# MaTouch_ESP32-S3_Rotary_IPS_Display_with.net
KiCad netlist of a schematic drawn in EAGLE
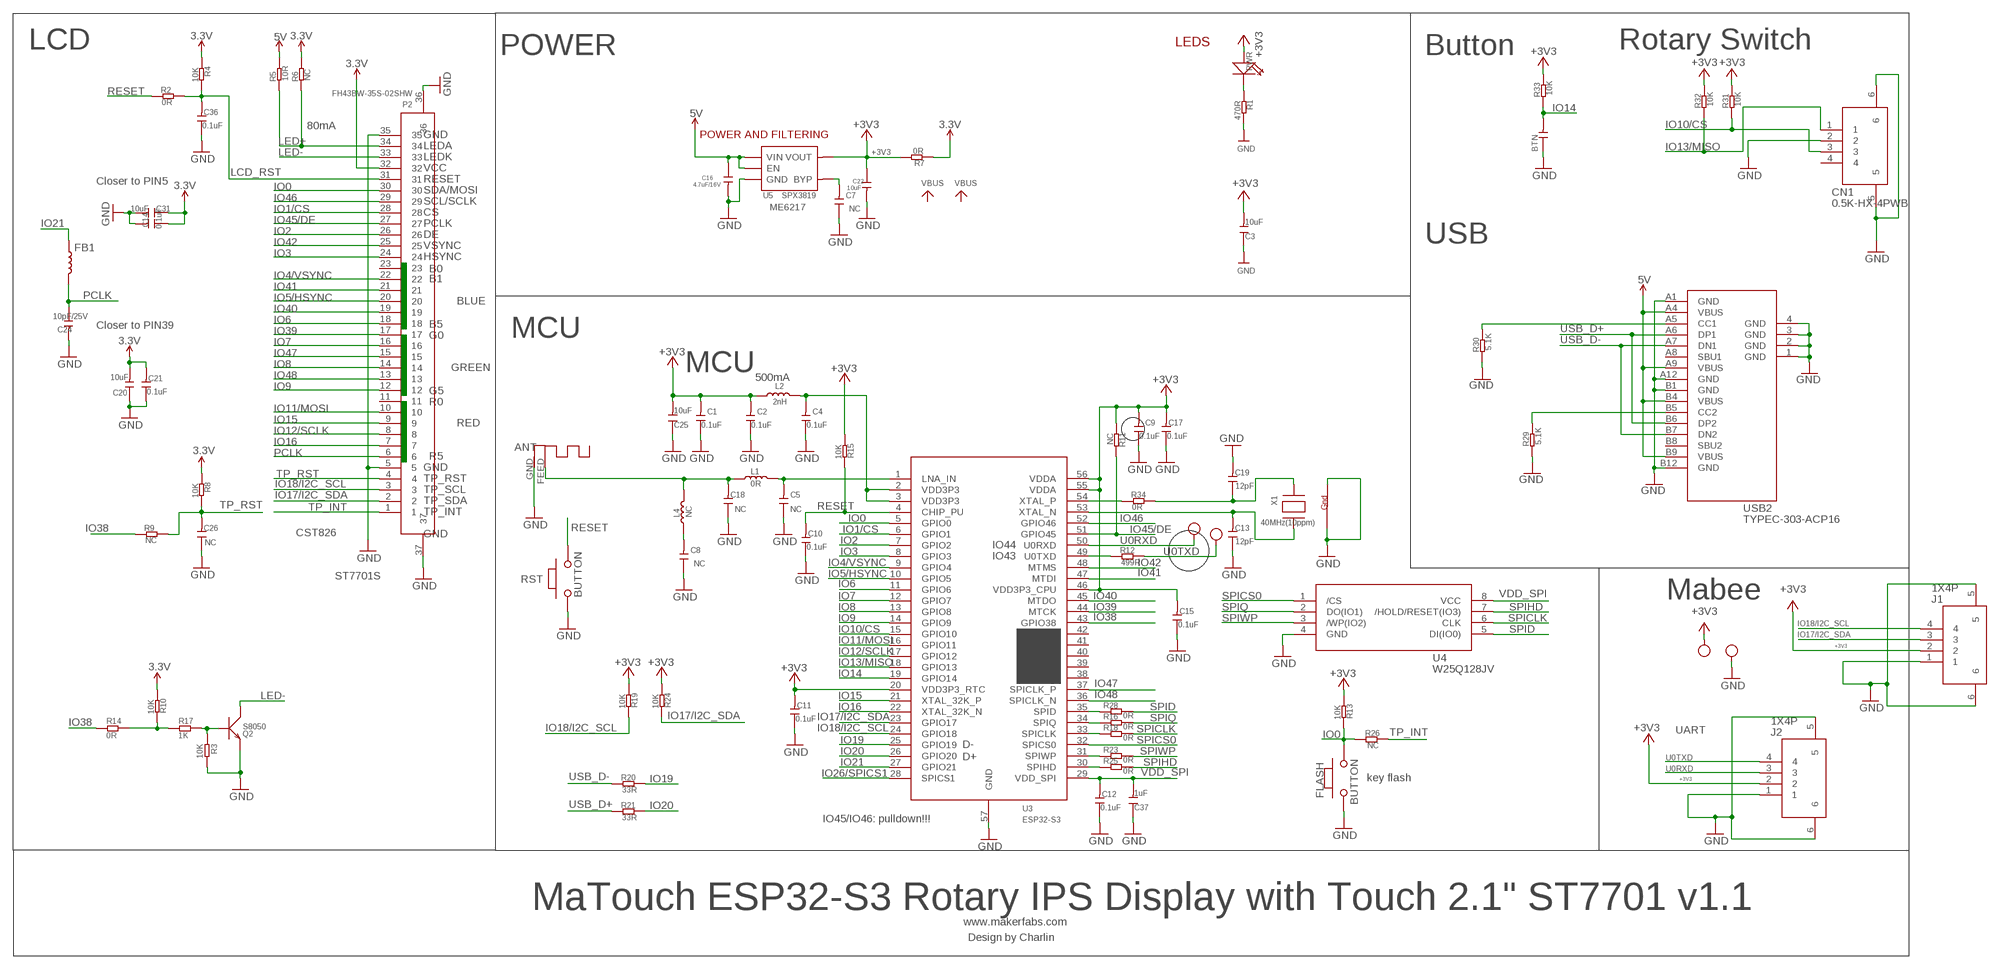
[diagram p0: schematic, sheet 1]

(export (version "E")
  (design (tool "Eeschema 10.0.6"))
  (components
    (comp (ref "3V3")
      (value "TEST-POINT'4545'")
      (footprint "eagle-import:TP-D45MIL")
      (fields (field (name "PARTNO") "DNP") (field (name "PARTNO_1") "DNP"))
      (libsource (lib "eagle-import") (part "TEST-POINT'4545'"))
    )
    (comp (ref "ANT1")
      (value "ANTENNA")
      (footprint "eagle-import:RN-ANT")
      (libsource (lib "eagle-import") (part "ANTENNA"))
    )
    (comp (ref "BTN")
      (value "C'5.08'")
      (footprint "eagle-import:CERAMIC-5.08")
      (libsource (lib "eagle-import") (part "C'5.08'"))
    )
    (comp (ref "C1")
      (value "0.1uF")
      (footprint "eagle-import:DISCRETE_C0402")
      (libsource (lib "eagle-import") (part "DISCRETE_C-0402"))
    )
    (comp (ref "C2")
      (value "0.1uF")
      (footprint "eagle-import:DISCRETE_C0402")
      (libsource (lib "eagle-import") (part "DISCRETE_C-0402"))
    )
    (comp (ref "C3")
      (value "10uF")
      (footprint "eagle-import:DISCRETE_C0603")
      (libsource (lib "eagle-import") (part "DISCRETE_C-0603"))
    )
    (comp (ref "C4")
      (value "0.1uF")
      (footprint "eagle-import:DISCRETE_C0402")
      (libsource (lib "eagle-import") (part "DISCRETE_C-0402"))
    )
    (comp (ref "C5")
      (value "NC")
      (footprint "eagle-import:DISCRETE_C0402")
      (libsource (lib "eagle-import") (part "DISCRETE_C-0402"))
    )
    (comp (ref "C7")
      (value "NC")
      (footprint "eagle-import:DISCRETE_C0402")
      (libsource (lib "eagle-import") (part "DISCRETE_C-0402"))
    )
    (comp (ref "C8")
      (value "NC")
      (footprint "eagle-import:DISCRETE_C0402")
      (libsource (lib "eagle-import") (part "DISCRETE_C-0402"))
    )
    (comp (ref "C9")
      (value "0.1uF")
      (footprint "eagle-import:DISCRETE_C0402")
      (libsource (lib "eagle-import") (part "DISCRETE_C-0402"))
    )
    (comp (ref "C10")
      (value "0.1uF")
      (footprint "eagle-import:DISCRETE_C0402")
      (libsource (lib "eagle-import") (part "DISCRETE_C-0402"))
    )
    (comp (ref "C11")
      (value "0.1uF")
      (footprint "eagle-import:DISCRETE_C0402")
      (libsource (lib "eagle-import") (part "DISCRETE_C-0402"))
    )
    (comp (ref "C12")
      (value "0.1uF")
      (footprint "eagle-import:DISCRETE_C0402")
      (libsource (lib "eagle-import") (part "DISCRETE_C-0402"))
    )
    (comp (ref "C13")
      (value "12pF")
      (footprint "eagle-import:DISCRETE_C0402")
      (libsource (lib "eagle-import") (part "DISCRETE_C-0402"))
    )
    (comp (ref "C14")
      (value "0.1uF")
      (footprint "eagle-import:DISCRETE_C0402")
      (libsource (lib "eagle-import") (part "DISCRETE_C-0402"))
    )
    (comp (ref "C15")
      (value "0.1uF")
      (footprint "eagle-import:DISCRETE_C0402")
      (libsource (lib "eagle-import") (part "DISCRETE_C-0402"))
    )
    (comp (ref "C16")
      (value "4.7uF/16V")
      (footprint "eagle-import:0603")
      (libsource (lib "eagle-import") (part "C-0603"))
    )
    (comp (ref "C17")
      (value "0.1uF")
      (footprint "eagle-import:DISCRETE_C0402")
      (libsource (lib "eagle-import") (part "DISCRETE_C-0402"))
    )
    (comp (ref "C18")
      (value "NC")
      (footprint "eagle-import:DISCRETE_C0402")
      (libsource (lib "eagle-import") (part "DISCRETE_C-0402"))
    )
    (comp (ref "C19")
      (value "12pF")
      (footprint "eagle-import:DISCRETE_C0402")
      (libsource (lib "eagle-import") (part "DISCRETE_C-0402"))
    )
    (comp (ref "C20")
      (value "10uF")
      (footprint "eagle-import:DISCRETE_C0603")
      (libsource (lib "eagle-import") (part "DISCRETE_C-0603"))
    )
    (comp (ref "C21")
      (value "0.1uF")
      (footprint "eagle-import:DISCRETE_C0402")
      (libsource (lib "eagle-import") (part "DISCRETE_C-0402"))
    )
    (comp (ref "C22")
      (value "10uF")
      (footprint "eagle-import:0603")
      (libsource (lib "eagle-import") (part "C-0603"))
    )
    (comp (ref "C24")
      (value "10pF/25V")
      (footprint "eagle-import:DISCRETE_C0402")
      (libsource (lib "eagle-import") (part "DISCRETE_C-0402"))
    )
    (comp (ref "C25")
      (value "10uF")
      (footprint "eagle-import:DISCRETE_C0603")
      (libsource (lib "eagle-import") (part "DISCRETE_C-0603"))
    )
    (comp (ref "C26")
      (value "NC")
      (footprint "eagle-import:DISCRETE_C0402")
      (libsource (lib "eagle-import") (part "DISCRETE_C-0402"))
    )
    (comp (ref "C31")
      (value "10uF")
      (footprint "eagle-import:DISCRETE_C0603")
      (libsource (lib "eagle-import") (part "DISCRETE_C-0603"))
    )
    (comp (ref "C36")
      (value "0.1uF")
      (footprint "eagle-import:DISCRETE_C0402")
      (libsource (lib "eagle-import") (part "DISCRETE_C-0402"))
    )
    (comp (ref "C37")
      (value "1uF")
      (footprint "eagle-import:DISCRETE_C0603")
      (libsource (lib "eagle-import") (part "DISCRETE_C-0603"))
    )
    (comp (ref "CN1")
      (value "0.5K-HX-4PWB")
      (footprint "eagle-import:0.5K-HX-4PWB")
      (libsource (lib "eagle-import") (part "0.5K-HX-4PWB"))
    )
    (comp (ref "FB1")
      (value "INDUCTORFB-30OHM")
      (footprint "eagle-import:0603")
      (libsource (lib "eagle-import") (part "INDUCTORFB-30OHM"))
    )
    (comp (ref "FLASH")
      (value "BUTTON")
      (footprint "eagle-import:157SW")
      (libsource (lib "eagle-import") (part "PB157"))
    )
    (comp (ref "GND")
      (value "TEST-POINT'4545'")
      (footprint "eagle-import:TP-D45MIL")
      (fields (field (name "PARTNO") "DNP") (field (name "PARTNO_1") "DNP"))
      (libsource (lib "eagle-import") (part "TEST-POINT'4545'"))
    )
    (comp (ref "J1")
      (value "1X4P")
      (footprint "eagle-import:1X4P-SMT1.25MM")
      (libsource (lib "eagle-import") (part "1X4P"))
    )
    (comp (ref "J2")
      (value "1X4P")
      (footprint "eagle-import:1X4P-SMT1.25MM")
      (libsource (lib "eagle-import") (part "1X4P"))
    )
    (comp (ref "L1")
      (value "0R")
      (footprint "eagle-import:DISCRETE_L0402")
      (libsource (lib "eagle-import") (part "DISCRETE_L0402"))
    )
    (comp (ref "L2")
      (value "2nH")
      (footprint "eagle-import:DISCRETE_L0603")
      (libsource (lib "eagle-import") (part "DISCRETE_L0603"))
    )
    (comp (ref "L4")
      (value "NC")
      (footprint "eagle-import:DISCRETE_L0402")
      (libsource (lib "eagle-import") (part "DISCRETE_L0402"))
    )
    (comp (ref "P2")
      (value "FH43BW-35S-02SHW")
      (footprint "eagle-import:1_35P-SMT0.4MM")
      (libsource (lib "eagle-import") (part "FH43BW-35S-02SHW"))
    )
    (comp (ref "PWR")
      (value "DISCRETE_LED0603")
      (footprint "eagle-import:DISCRETE_LED-0603")
      (libsource (lib "eagle-import") (part "DISCRETE_LED0603"))
    )
    (comp (ref "Q2")
      (value "S8050")
      (footprint "eagle-import:SOT23")
      (libsource (lib "eagle-import") (part "TRANSISTOR-NPN-SOT23"))
    )
    (comp (ref "R1")
      (value "470R")
      (footprint "eagle-import:DISCRETE_R0402")
      (libsource (lib "eagle-import") (part "DISCRETE_R-0402"))
    )
    (comp (ref "R2")
      (value "0R")
      (footprint "eagle-import:DISCRETE_R0402")
      (libsource (lib "eagle-import") (part "DISCRETE_R-0402"))
    )
    (comp (ref "R3")
      (value "10K")
      (footprint "eagle-import:DISCRETE_R0402")
      (libsource (lib "eagle-import") (part "DISCRETE_R-0402"))
    )
    (comp (ref "R4")
      (value "10K")
      (footprint "eagle-import:DISCRETE_R0402")
      (libsource (lib "eagle-import") (part "DISCRETE_R-0402"))
    )
    (comp (ref "R5")
      (value "10R")
      (footprint "eagle-import:DISCRETE_R0402")
      (libsource (lib "eagle-import") (part "DISCRETE_R-0402"))
    )
    (comp (ref "R6")
      (value "NC")
      (footprint "eagle-import:DISCRETE_R0402")
      (libsource (lib "eagle-import") (part "DISCRETE_R-0402"))
    )
    (comp (ref "R7")
      (value "0R")
      (footprint "eagle-import:DISCRETE_R0402")
      (libsource (lib "eagle-import") (part "DISCRETE_R-0402"))
    )
    (comp (ref "R8")
      (value "10K")
      (footprint "eagle-import:DISCRETE_R0402")
      (libsource (lib "eagle-import") (part "DISCRETE_R-0402"))
    )
    (comp (ref "R9")
      (value "NC")
      (footprint "eagle-import:DISCRETE_R0402")
      (libsource (lib "eagle-import") (part "DISCRETE_R-0402"))
    )
    (comp (ref "R10")
      (value "10K")
      (footprint "eagle-import:DISCRETE_R0402")
      (libsource (lib "eagle-import") (part "DISCRETE_R-0402"))
    )
    (comp (ref "R11")
      (value "NC")
      (footprint "eagle-import:DISCRETE_R0402")
      (libsource (lib "eagle-import") (part "DISCRETE_R-0402"))
    )
    (comp (ref "R12")
      (value "499R")
      (footprint "eagle-import:DISCRETE_R0402")
      (libsource (lib "eagle-import") (part "DISCRETE_R-0402"))
    )
    (comp (ref "R13")
      (value "10K")
      (footprint "eagle-import:DISCRETE_R0402")
      (libsource (lib "eagle-import") (part "DISCRETE_R-0402"))
    )
    (comp (ref "R14")
      (value "0R")
      (footprint "eagle-import:DISCRETE_R0402")
      (libsource (lib "eagle-import") (part "DISCRETE_R-0402"))
    )
    (comp (ref "R15")
      (value "10K")
      (footprint "eagle-import:DISCRETE_R0402")
      (libsource (lib "eagle-import") (part "DISCRETE_R-0402"))
    )
    (comp (ref "R16")
      (value "0R")
      (footprint "eagle-import:DISCRETE_R0402")
      (libsource (lib "eagle-import") (part "DISCRETE_R-0402"))
    )
    (comp (ref "R17")
      (value "1K")
      (footprint "eagle-import:DISCRETE_R0402")
      (libsource (lib "eagle-import") (part "DISCRETE_R-0402"))
    )
    (comp (ref "R18")
      (value "0R")
      (footprint "eagle-import:DISCRETE_R0402")
      (libsource (lib "eagle-import") (part "DISCRETE_R-0402"))
    )
    (comp (ref "R19")
      (value "10K")
      (footprint "eagle-import:DISCRETE_R0402")
      (libsource (lib "eagle-import") (part "DISCRETE_R-0402"))
    )
    (comp (ref "R20")
      (value "33R")
      (footprint "eagle-import:DISCRETE_R0402")
      (libsource (lib "eagle-import") (part "DISCRETE_R-0402"))
    )
    (comp (ref "R21")
      (value "33R")
      (footprint "eagle-import:DISCRETE_R0402")
      (libsource (lib "eagle-import") (part "DISCRETE_R-0402"))
    )
    (comp (ref "R23")
      (value "0R")
      (footprint "eagle-import:DISCRETE_R0402")
      (libsource (lib "eagle-import") (part "DISCRETE_R-0402"))
    )
    (comp (ref "R24")
      (value "10K")
      (footprint "eagle-import:DISCRETE_R0402")
      (libsource (lib "eagle-import") (part "DISCRETE_R-0402"))
    )
    (comp (ref "R25")
      (value "0R")
      (footprint "eagle-import:DISCRETE_R0402")
      (libsource (lib "eagle-import") (part "DISCRETE_R-0402"))
    )
    (comp (ref "R26")
      (value "NC")
      (footprint "eagle-import:DISCRETE_R0402")
      (libsource (lib "eagle-import") (part "DISCRETE_R-0402"))
    )
    (comp (ref "R28")
      (value "0R")
      (footprint "eagle-import:DISCRETE_R0402")
      (libsource (lib "eagle-import") (part "DISCRETE_R-0402"))
    )
    (comp (ref "R29")
      (value "5.1K")
      (footprint "eagle-import:DISCRETE_R0402")
      (libsource (lib "eagle-import") (part "DISCRETE_R-0402"))
    )
    (comp (ref "R30")
      (value "5.1K")
      (footprint "eagle-import:DISCRETE_R0402")
      (libsource (lib "eagle-import") (part "DISCRETE_R-0402"))
    )
    (comp (ref "R31")
      (value "10K")
      (footprint "eagle-import:DISCRETE_R0402")
      (libsource (lib "eagle-import") (part "DISCRETE_R-0402"))
    )
    (comp (ref "R32")
      (value "10K")
      (footprint "eagle-import:DISCRETE_R0402")
      (libsource (lib "eagle-import") (part "DISCRETE_R-0402"))
    )
    (comp (ref "R33")
      (value "10K")
      (footprint "eagle-import:DISCRETE_R0402")
      (libsource (lib "eagle-import") (part "DISCRETE_R-0402"))
    )
    (comp (ref "R34")
      (value "0R")
      (footprint "eagle-import:DISCRETE_R0402")
      (libsource (lib "eagle-import") (part "DISCRETE_R-0402"))
    )
    (comp (ref "RST")
      (value "BUTTON")
      (footprint "eagle-import:157SW")
      (libsource (lib "eagle-import") (part "PB157"))
    )
    (comp (ref "RX")
      (value "TEST-POINT'4545'")
      (footprint "eagle-import:TP-D45MIL")
      (fields (field (name "PARTNO") "DNP") (field (name "PARTNO_1") "DNP"))
      (libsource (lib "eagle-import") (part "TEST-POINT'4545'"))
    )
    (comp (ref "TX")
      (value "TEST-POINT'4545'")
      (footprint "eagle-import:TP-D45MIL")
      (fields (field (name "PARTNO") "DNP") (field (name "PARTNO_1") "DNP"))
      (libsource (lib "eagle-import") (part "TEST-POINT'4545'"))
    )
    (comp (ref "U3")
      (value "ESP32-S3")
      (footprint "eagle-import:QFN56-7_7MM")
      (libsource (lib "eagle-import") (part "ESP32-S3"))
    )
    (comp (ref "U4")
      (value "W25Q128JV")
      (footprint "eagle-import:SOIC-8-208MIL")
      (libsource (lib "eagle-import") (part "W25Q128JV"))
    )
    (comp (ref "U5")
      (value "SPX3819")
      (footprint "eagle-import:SOT23-5")
      (libsource (lib "eagle-import") (part "SPX3819"))
    )
    (comp (ref "USB2")
      (value "TYPEC-303-ACP16")
      (footprint "eagle-import:TYPEC-303-SMD16")
      (libsource (lib "eagle-import") (part "TYPEC-303-ACP16"))
    )
    (comp (ref "X1")
      (value "40MHz(10ppm)")
      (footprint "eagle-import:NX3225")
      (libsource (lib "eagle-import") (part "XTAL-4-3225"))
    )
  )
  (nets
    (net (code "1") (name "+3V3") (class "Default")
      (node (ref "3V3") (pin "T") (pinfunction "T_T") (pintype "bidirectional"))
      (node (ref "C1") (pin "2") (pinfunction "2_2") (pintype "passive"))
      (node (ref "C11") (pin "2") (pinfunction "2_2") (pintype "passive"))
      (node (ref "C15") (pin "2") (pinfunction "2_2") (pintype "passive"))
      (node (ref "C17") (pin "2") (pinfunction "2_2") (pintype "passive"))
      (node (ref "C2") (pin "2") (pinfunction "2_2") (pintype "passive"))
      (node (ref "C22") (pin "1") (pinfunction "1_1") (pintype "passive"))
      (node (ref "C25") (pin "2") (pinfunction "2_2") (pintype "passive"))
      (node (ref "C3") (pin "2") (pinfunction "2_2") (pintype "passive"))
      (node (ref "C9") (pin "2") (pinfunction "2_2") (pintype "passive"))
      (node (ref "J1") (pin "2") (pinfunction "2_2") (pintype "bidirectional"))
      (node (ref "J2") (pin "2") (pinfunction "2_2") (pintype "bidirectional"))
      (node (ref "L2") (pin "1") (pinfunction "1_1") (pintype "passive"))
      (node (ref "PWR") (pin "+") (pinfunction "+_+") (pintype "passive"))
      (node (ref "R11") (pin "2") (pinfunction "2_2") (pintype "passive"))
      (node (ref "R13") (pin "2") (pinfunction "2_2") (pintype "passive"))
      (node (ref "R15") (pin "2") (pinfunction "2_2") (pintype "passive"))
      (node (ref "R19") (pin "2") (pinfunction "2_2") (pintype "passive"))
      (node (ref "R24") (pin "2") (pinfunction "2_2") (pintype "passive"))
      (node (ref "R31") (pin "1") (pinfunction "1_1") (pintype "passive"))
      (node (ref "R32") (pin "1") (pinfunction "1_1") (pintype "passive"))
      (node (ref "R33") (pin "1") (pinfunction "1_1") (pintype "passive"))
      (node (ref "R7") (pin "1") (pinfunction "1_1") (pintype "passive"))
      (node (ref "U3") (pin "20") (pinfunction "VDD3P3_RTC_20") (pintype "bidirectional"))
      (node (ref "U3") (pin "46") (pinfunction "VDD3P3_CPU_46") (pintype "bidirectional"))
      (node (ref "U3") (pin "55") (pinfunction "VDDA_55") (pintype "bidirectional"))
      (node (ref "U3") (pin "56") (pinfunction "VDDA_56") (pintype "bidirectional"))
      (node (ref "U5") (pin "5") (pinfunction "VOUT_5") (pintype "bidirectional"))
    )
    (net (code "2") (name "/IO0") (class "Default")
      (node (ref "FLASH") (pin "2") (pinfunction "2_2") (pintype "passive"))
      (node (ref "P2") (pin "30") (pinfunction "30_30") (pintype "bidirectional"))
      (node (ref "R13") (pin "1") (pinfunction "1_1") (pintype "passive"))
      (node (ref "R26") (pin "2") (pinfunction "2_2") (pintype "passive"))
      (node (ref "U3") (pin "5") (pinfunction "GPIO0_5") (pintype "bidirectional"))
    )
    (net (code "3") (name "/IO1{slash}CS") (class "Default")
      (node (ref "P2") (pin "28") (pinfunction "28_28") (pintype "bidirectional"))
      (node (ref "U3") (pin "6") (pinfunction "GPIO1_6") (pintype "bidirectional"))
    )
    (net (code "4") (name "/IO2") (class "Default")
      (node (ref "P2") (pin "26") (pinfunction "26_26") (pintype "bidirectional"))
      (node (ref "U3") (pin "7") (pinfunction "GPIO2_7") (pintype "bidirectional"))
    )
    (net (code "5") (name "/IO3") (class "Default")
      (node (ref "P2") (pin "24") (pinfunction "24_24") (pintype "bidirectional"))
      (node (ref "U3") (pin "8") (pinfunction "GPIO3_8") (pintype "bidirectional"))
    )
    (net (code "6") (name "/IO4{slash}VSYNC") (class "Default")
      (node (ref "P2") (pin "22") (pinfunction "22_22") (pintype "bidirectional"))
      (node (ref "U3") (pin "9") (pinfunction "GPIO4_9") (pintype "bidirectional"))
    )
    (net (code "7") (name "/IO5{slash}HSYNC") (class "Default")
      (node (ref "P2") (pin "20") (pinfunction "20_20") (pintype "bidirectional"))
      (node (ref "U3") (pin "10") (pinfunction "GPIO5_10") (pintype "bidirectional"))
    )
    (net (code "8") (name "/IO6") (class "Default")
      (node (ref "P2") (pin "18") (pinfunction "18_18") (pintype "bidirectional"))
      (node (ref "U3") (pin "11") (pinfunction "GPIO6_11") (pintype "bidirectional"))
    )
    (net (code "9") (name "/IO7") (class "Default")
      (node (ref "P2") (pin "16") (pinfunction "16_16") (pintype "bidirectional"))
      (node (ref "U3") (pin "12") (pinfunction "GPIO7_12") (pintype "bidirectional"))
    )
    (net (code "10") (name "/IO8") (class "Default")
      (node (ref "P2") (pin "14") (pinfunction "14_14") (pintype "bidirectional"))
      (node (ref "U3") (pin "13") (pinfunction "GPIO8_13") (pintype "bidirectional"))
    )
    (net (code "11") (name "/IO9") (class "Default")
      (node (ref "P2") (pin "12") (pinfunction "12_12") (pintype "bidirectional"))
      (node (ref "U3") (pin "14") (pinfunction "GPIO9_14") (pintype "bidirectional"))
    )
    (net (code "12") (name "/IO10{slash}CS") (class "Default")
      (node (ref "CN1") (pin "3") (pinfunction "3_3") (pintype "bidirectional"))
      (node (ref "R31") (pin "2") (pinfunction "2_2") (pintype "passive"))
      (node (ref "U3") (pin "15") (pinfunction "GPIO10_15") (pintype "bidirectional"))
    )
    (net (code "13") (name "/IO11{slash}MOSI") (class "Default")
      (node (ref "P2") (pin "10") (pinfunction "10_10") (pintype "bidirectional"))
      (node (ref "U3") (pin "16") (pinfunction "GPIO11_16") (pintype "bidirectional"))
    )
    (net (code "14") (name "/IO12{slash}SCLK") (class "Default")
      (node (ref "P2") (pin "8") (pinfunction "8_8") (pintype "bidirectional"))
      (node (ref "U3") (pin "17") (pinfunction "GPIO12_17") (pintype "bidirectional"))
    )
    (net (code "15") (name "/IO13{slash}MISO") (class "Default")
      (node (ref "CN1") (pin "1") (pinfunction "1_1") (pintype "bidirectional"))
      (node (ref "R32") (pin "2") (pinfunction "2_2") (pintype "passive"))
      (node (ref "U3") (pin "18") (pinfunction "GPIO13_18") (pintype "bidirectional"))
    )
    (net (code "16") (name "/IO14") (class "Default")
      (node (ref "BTN") (pin "2") (pinfunction "2_2") (pintype "passive"))
      (node (ref "R33") (pin "2") (pinfunction "2_2") (pintype "passive"))
      (node (ref "U3") (pin "19") (pinfunction "GPIO14_19") (pintype "bidirectional"))
    )
    (net (code "17") (name "/IO15") (class "Default")
      (node (ref "P2") (pin "9") (pinfunction "9_9") (pintype "bidirectional"))
      (node (ref "U3") (pin "21") (pinfunction "XTAL_32K_P_21") (pintype "bidirectional"))
    )
    (net (code "18") (name "/IO16") (class "Default")
      (node (ref "P2") (pin "7") (pinfunction "7_7") (pintype "bidirectional"))
      (node (ref "U3") (pin "22") (pinfunction "XTAL_32K_N_22") (pintype "bidirectional"))
    )
    (net (code "19") (name "/IO17{slash}I2C_SDA") (class "Default")
      (node (ref "J1") (pin "3") (pinfunction "3_3") (pintype "bidirectional"))
      (node (ref "P2") (pin "2") (pinfunction "2_2") (pintype "bidirectional"))
      (node (ref "R24") (pin "1") (pinfunction "1_1") (pintype "passive"))
      (node (ref "U3") (pin "23") (pinfunction "GPIO17_23") (pintype "bidirectional"))
    )
    (net (code "20") (name "/IO18{slash}I2C_SCL") (class "Default")
      (node (ref "J1") (pin "4") (pinfunction "4_4") (pintype "bidirectional"))
      (node (ref "P2") (pin "3") (pinfunction "3_3") (pintype "bidirectional"))
      (node (ref "R19") (pin "1") (pinfunction "1_1") (pintype "passive"))
      (node (ref "U3") (pin "24") (pinfunction "GPIO18_24") (pintype "bidirectional"))
    )
    (net (code "21") (name "/IO19") (class "Default")
      (node (ref "R20") (pin "1") (pinfunction "1_1") (pintype "passive"))
      (node (ref "U3") (pin "25") (pinfunction "GPIO19_25") (pintype "bidirectional"))
    )
    (net (code "22") (name "/IO20") (class "Default")
      (node (ref "R21") (pin "1") (pinfunction "1_1") (pintype "passive"))
      (node (ref "U3") (pin "26") (pinfunction "GPIO20_26") (pintype "bidirectional"))
    )
    (net (code "23") (name "/IO21") (class "Default")
      (node (ref "FB1") (pin "1") (pinfunction "1_1") (pintype "passive"))
      (node (ref "U3") (pin "27") (pinfunction "GPIO21_27") (pintype "bidirectional"))
    )
    (net (code "24") (name "/IO26{slash}SPICS1") (class "Default")
      (node (ref "U3") (pin "28") (pinfunction "SPICS1_28") (pintype "bidirectional"))
    )
    (net (code "25") (name "/IO38") (class "Default")
      (node (ref "R14") (pin "2") (pinfunction "2_2") (pintype "passive"))
      (node (ref "R9") (pin "2") (pinfunction "2_2") (pintype "passive"))
      (node (ref "U3") (pin "43") (pinfunction "GPIO38_43") (pintype "bidirectional"))
    )
    (net (code "26") (name "/IO39") (class "Default")
      (node (ref "P2") (pin "17") (pinfunction "17_17") (pintype "bidirectional"))
      (node (ref "U3") (pin "44") (pinfunction "MTCK_44") (pintype "bidirectional"))
    )
    (net (code "27") (name "/IO40") (class "Default")
      (node (ref "P2") (pin "19") (pinfunction "19_19") (pintype "bidirectional"))
      (node (ref "U3") (pin "45") (pinfunction "MTDO_45") (pintype "bidirectional"))
    )
    (net (code "28") (name "/IO41") (class "Default")
      (node (ref "P2") (pin "21") (pinfunction "21_21") (pintype "bidirectional"))
      (node (ref "U3") (pin "47") (pinfunction "MTDI_47") (pintype "bidirectional"))
    )
    (net (code "29") (name "/IO42") (class "Default")
      (node (ref "P2") (pin "25") (pinfunction "25_25") (pintype "bidirectional"))
      (node (ref "U3") (pin "48") (pinfunction "MTMS_48") (pintype "bidirectional"))
    )
    (net (code "30") (name "/IO45{slash}DE") (class "Default")
      (node (ref "P2") (pin "27") (pinfunction "27_27") (pintype "bidirectional"))
      (node (ref "R11") (pin "1") (pinfunction "1_1") (pintype "passive"))
      (node (ref "U3") (pin "51") (pinfunction "GPIO45_51") (pintype "bidirectional"))
    )
    (net (code "31") (name "/IO46") (class "Default")
      (node (ref "P2") (pin "29") (pinfunction "29_29") (pintype "bidirectional"))
      (node (ref "U3") (pin "52") (pinfunction "GPIO46_52") (pintype "bidirectional"))
    )
    (net (code "32") (name "/IO47") (class "Default")
      (node (ref "P2") (pin "15") (pinfunction "15_15") (pintype "bidirectional"))
      (node (ref "U3") (pin "37") (pinfunction "SPICLK_P_37") (pintype "bidirectional"))
    )
    (net (code "33") (name "/IO48") (class "Default")
      (node (ref "P2") (pin "13") (pinfunction "13_13") (pintype "bidirectional"))
      (node (ref "U3") (pin "36") (pinfunction "SPICLK_N_36") (pintype "bidirectional"))
    )
    (net (code "34") (name "/LCD_RST") (class "Default")
      (node (ref "C36") (pin "2") (pinfunction "2_2") (pintype "passive"))
      (node (ref "P2") (pin "31") (pinfunction "31_31") (pintype "bidirectional"))
      (node (ref "R2") (pin "1") (pinfunction "1_1") (pintype "passive"))
      (node (ref "R4") (pin "1") (pinfunction "1_1") (pintype "passive"))
    )
    (net (code "35") (name "/LED+") (class "Default")
      (node (ref "P2") (pin "34") (pinfunction "34_34") (pintype "bidirectional"))
      (node (ref "R5") (pin "2") (pinfunction "2_2") (pintype "passive"))
      (node (ref "R6") (pin "2") (pinfunction "2_2") (pintype "passive"))
    )
    (net (code "36") (name "/LED-") (class "Default")
      (node (ref "P2") (pin "33") (pinfunction "33_33") (pintype "bidirectional"))
      (node (ref "Q2") (pin "3") (pinfunction "C_3") (pintype "passive"))
    )
    (net (code "37") (name "/PCLK") (class "Default")
      (node (ref "C24") (pin "1") (pinfunction "1_1") (pintype "passive"))
      (node (ref "FB1") (pin "2") (pinfunction "2_2") (pintype "passive"))
      (node (ref "P2") (pin "6") (pinfunction "6_6") (pintype "bidirectional"))
    )
    (net (code "38") (name "/RESET") (class "Default")
      (node (ref "C10") (pin "2") (pinfunction "2_2") (pintype "passive"))
      (node (ref "R15") (pin "1") (pinfunction "1_1") (pintype "passive"))
      (node (ref "R2") (pin "2") (pinfunction "2_2") (pintype "passive"))
      (node (ref "RST") (pin "2") (pinfunction "2_2") (pintype "passive"))
      (node (ref "U3") (pin "4") (pinfunction "CHIP_PU_4") (pintype "bidirectional"))
    )
    (net (code "39") (name "/SPICLK") (class "Default")
      (node (ref "R18") (pin "1") (pinfunction "1_1") (pintype "passive"))
      (node (ref "U4") (pin "6") (pinfunction "CLK_6") (pintype "bidirectional"))
    )
    (net (code "40") (name "/SPICS0") (class "Default")
      (node (ref "U3") (pin "32") (pinfunction "SPICS0_32") (pintype "bidirectional"))
      (node (ref "U4") (pin "1") (pinfunction "/CS_1") (pintype "bidirectional"))
    )
    (net (code "41") (name "/SPID") (class "Default")
      (node (ref "R28") (pin "1") (pinfunction "1_1") (pintype "passive"))
      (node (ref "U4") (pin "5") (pinfunction "DI(IO0)_5") (pintype "bidirectional"))
    )
    (net (code "42") (name "/SPIHD") (class "Default")
      (node (ref "R25") (pin "1") (pinfunction "1_1") (pintype "passive"))
      (node (ref "U4") (pin "7") (pinfunction "/HOLD/RESET(IO3)_7") (pintype "bidirectional"))
    )
    (net (code "43") (name "/SPIQ") (class "Default")
      (node (ref "R16") (pin "1") (pinfunction "1_1") (pintype "passive"))
      (node (ref "U4") (pin "2") (pinfunction "DO(IO1)_2") (pintype "bidirectional"))
    )
    (net (code "44") (name "/SPIWP") (class "Default")
      (node (ref "R23") (pin "1") (pinfunction "1_1") (pintype "passive"))
      (node (ref "U4") (pin "3") (pinfunction "/WP(IO2)_3") (pintype "bidirectional"))
    )
    (net (code "45") (name "/TP_INT") (class "Default")
      (node (ref "P2") (pin "1") (pinfunction "1_1") (pintype "bidirectional"))
      (node (ref "R26") (pin "1") (pinfunction "1_1") (pintype "passive"))
    )
    (net (code "46") (name "/TP_RST") (class "Default")
      (node (ref "C26") (pin "2") (pinfunction "2_2") (pintype "passive"))
      (node (ref "P2") (pin "4") (pinfunction "4_4") (pintype "bidirectional"))
      (node (ref "R8") (pin "1") (pinfunction "1_1") (pintype "passive"))
      (node (ref "R9") (pin "1") (pinfunction "1_1") (pintype "passive"))
    )
    (net (code "47") (name "/U0RXD") (class "Default")
      (node (ref "J2") (pin "3") (pinfunction "3_3") (pintype "bidirectional"))
      (node (ref "RX") (pin "T") (pinfunction "T_T") (pintype "bidirectional"))
      (node (ref "U3") (pin "50") (pinfunction "U0RXD_50") (pintype "bidirectional"))
    )
    (net (code "48") (name "/U0TXD") (class "Default")
      (node (ref "J2") (pin "4") (pinfunction "4_4") (pintype "bidirectional"))
      (node (ref "R12") (pin "1") (pinfunction "1_1") (pintype "passive"))
      (node (ref "TX") (pin "T") (pinfunction "T_T") (pintype "bidirectional"))
    )
    (net (code "49") (name "/USB_D+") (class "Default")
      (node (ref "R21") (pin "2") (pinfunction "2_2") (pintype "passive"))
      (node (ref "USB2") (pin "A6") (pinfunction "DP1_A6") (pintype "bidirectional"))
      (node (ref "USB2") (pin "B6") (pinfunction "DP2_B6") (pintype "bidirectional"))
    )
    (net (code "50") (name "/USB_D-") (class "Default")
      (node (ref "R20") (pin "2") (pinfunction "2_2") (pintype "passive"))
      (node (ref "USB2") (pin "A7") (pinfunction "DN1_A7") (pintype "bidirectional"))
      (node (ref "USB2") (pin "B7") (pinfunction "DN2_B7") (pintype "bidirectional"))
    )
    (net (code "51") (name "/VDD_SPI") (class "Default")
      (node (ref "C12") (pin "2") (pinfunction "2_2") (pintype "passive"))
      (node (ref "C37") (pin "2") (pinfunction "2_2") (pintype "passive"))
      (node (ref "U3") (pin "29") (pinfunction "VDD_SPI_29") (pintype "bidirectional"))
      (node (ref "U4") (pin "8") (pinfunction "VCC_8") (pintype "bidirectional"))
    )
    (net (code "52") (name "3.3V") (class "Default")
      (node (ref "C14") (pin "1") (pinfunction "1_1") (pintype "passive"))
      (node (ref "C20") (pin "2") (pinfunction "2_2") (pintype "passive"))
      (node (ref "C21") (pin "2") (pinfunction "2_2") (pintype "passive"))
      (node (ref "C31") (pin "1") (pinfunction "1_1") (pintype "passive"))
      (node (ref "P2") (pin "32") (pinfunction "32_32") (pintype "bidirectional"))
      (node (ref "R10") (pin "2") (pinfunction "2_2") (pintype "passive"))
      (node (ref "R4") (pin "2") (pinfunction "2_2") (pintype "passive"))
      (node (ref "R6") (pin "1") (pinfunction "1_1") (pintype "passive"))
      (node (ref "R7") (pin "2") (pinfunction "2_2") (pintype "passive"))
      (node (ref "R8") (pin "2") (pinfunction "2_2") (pintype "passive"))
    )
    (net (code "53") (name "5V") (class "Default")
      (node (ref "C16") (pin "1") (pinfunction "1_1") (pintype "passive"))
      (node (ref "R5") (pin "1") (pinfunction "1_1") (pintype "passive"))
      (node (ref "U5") (pin "1") (pinfunction "VIN_1") (pintype "bidirectional"))
      (node (ref "U5") (pin "3") (pinfunction "EN_3") (pintype "bidirectional"))
      (node (ref "USB2") (pin "A4") (pinfunction "VBUS_A4") (pintype "bidirectional"))
      (node (ref "USB2") (pin "A9") (pinfunction "VBUS_A9") (pintype "bidirectional"))
      (node (ref "USB2") (pin "B4") (pinfunction "VBUS_B4") (pintype "bidirectional"))
      (node (ref "USB2") (pin "B9") (pinfunction "VBUS_B9") (pintype "bidirectional"))
    )
    (net (code "54") (name "GND") (class "Default")
      (node (ref "ANT1") (pin "GND") (pinfunction "GND_GND") (pintype "passive"))
      (node (ref "BTN") (pin "1") (pinfunction "1_1") (pintype "passive"))
      (node (ref "C1") (pin "1") (pinfunction "1_1") (pintype "passive"))
      (node (ref "C10") (pin "1") (pinfunction "1_1") (pintype "passive"))
      (node (ref "C11") (pin "1") (pinfunction "1_1") (pintype "passive"))
      (node (ref "C12") (pin "1") (pinfunction "1_1") (pintype "passive"))
      (node (ref "C13") (pin "1") (pinfunction "1_1") (pintype "passive"))
      (node (ref "C14") (pin "2") (pinfunction "2_2") (pintype "passive"))
      (node (ref "C15") (pin "1") (pinfunction "1_1") (pintype "passive"))
      (node (ref "C16") (pin "2") (pinfunction "2_2") (pintype "passive"))
      (node (ref "C17") (pin "1") (pinfunction "1_1") (pintype "passive"))
      (node (ref "C18") (pin "1") (pinfunction "1_1") (pintype "passive"))
      (node (ref "C19") (pin "2") (pinfunction "2_2") (pintype "passive"))
      (node (ref "C2") (pin "1") (pinfunction "1_1") (pintype "passive"))
      (node (ref "C20") (pin "1") (pinfunction "1_1") (pintype "passive"))
      (node (ref "C21") (pin "1") (pinfunction "1_1") (pintype "passive"))
      (node (ref "C22") (pin "2") (pinfunction "2_2") (pintype "passive"))
      (node (ref "C24") (pin "2") (pinfunction "2_2") (pintype "passive"))
      (node (ref "C25") (pin "1") (pinfunction "1_1") (pintype "passive"))
      (node (ref "C26") (pin "1") (pinfunction "1_1") (pintype "passive"))
      (node (ref "C3") (pin "1") (pinfunction "1_1") (pintype "passive"))
      (node (ref "C31") (pin "2") (pinfunction "2_2") (pintype "passive"))
      (node (ref "C36") (pin "1") (pinfunction "1_1") (pintype "passive"))
      (node (ref "C37") (pin "1") (pinfunction "1_1") (pintype "passive"))
      (node (ref "C4") (pin "1") (pinfunction "1_1") (pintype "passive"))
      (node (ref "C5") (pin "1") (pinfunction "1_1") (pintype "passive"))
      (node (ref "C7") (pin "1") (pinfunction "1_1") (pintype "passive"))
      (node (ref "C8") (pin "1") (pinfunction "1_1") (pintype "passive"))
      (node (ref "C9") (pin "1") (pinfunction "1_1") (pintype "passive"))
      (node (ref "CN1") (pin "2") (pinfunction "2_2") (pintype "bidirectional"))
      (node (ref "CN1") (pin "5") (pinfunction "5_5") (pintype "bidirectional"))
      (node (ref "CN1") (pin "6") (pinfunction "6_6") (pintype "bidirectional"))
      (node (ref "FLASH") (pin "1") (pinfunction "1_1") (pintype "passive"))
      (node (ref "GND") (pin "T") (pinfunction "T_T") (pintype "bidirectional"))
      (node (ref "J1") (pin "1") (pinfunction "1_1") (pintype "bidirectional"))
      (node (ref "J1") (pin "5") (pinfunction "5_5") (pintype "bidirectional"))
      (node (ref "J1") (pin "6") (pinfunction "6_6") (pintype "bidirectional"))
      (node (ref "J2") (pin "1") (pinfunction "1_1") (pintype "bidirectional"))
      (node (ref "J2") (pin "5") (pinfunction "5_5") (pintype "bidirectional"))
      (node (ref "J2") (pin "6") (pinfunction "6_6") (pintype "bidirectional"))
      (node (ref "P2") (pin "35") (pinfunction "35_35") (pintype "bidirectional"))
      (node (ref "P2") (pin "36") (pinfunction "36_36") (pintype "bidirectional"))
      (node (ref "P2") (pin "37") (pinfunction "37_37") (pintype "bidirectional"))
      (node (ref "P2") (pin "5") (pinfunction "5_5") (pintype "bidirectional"))
      (node (ref "Q2") (pin "2") (pinfunction "E_2") (pintype "passive"))
      (node (ref "R1") (pin "1") (pinfunction "1_1") (pintype "passive"))
      (node (ref "R29") (pin "2") (pinfunction "2_2") (pintype "passive"))
      (node (ref "R3") (pin "1") (pinfunction "1_1") (pintype "passive"))
      (node (ref "R30") (pin "2") (pinfunction "2_2") (pintype "passive"))
      (node (ref "RST") (pin "1") (pinfunction "1_1") (pintype "passive"))
      (node (ref "U3") (pin "57") (pinfunction "GND_57") (pintype "bidirectional"))
      (node (ref "U4") (pin "4") (pinfunction "GND_4") (pintype "bidirectional"))
      (node (ref "U5") (pin "2") (pinfunction "GND_2") (pintype "bidirectional"))
      (node (ref "USB2") (pin "1") (pinfunction "GND_1") (pintype "bidirectional"))
      (node (ref "USB2") (pin "2") (pinfunction "GND_2") (pintype "bidirectional"))
      (node (ref "USB2") (pin "3") (pinfunction "GND_3") (pintype "bidirectional"))
      (node (ref "USB2") (pin "4") (pinfunction "GND_4") (pintype "bidirectional"))
      (node (ref "USB2") (pin "A1") (pinfunction "GND_A1") (pintype "bidirectional"))
      (node (ref "USB2") (pin "A12") (pinfunction "GND_A12") (pintype "bidirectional"))
      (node (ref "USB2") (pin "B1") (pinfunction "GND_B1") (pintype "bidirectional"))
      (node (ref "USB2") (pin "B12") (pinfunction "GND_B12") (pintype "bidirectional"))
      (node (ref "X1") (pin "2") (pinfunction "G2_2") (pintype "power_in"))
      (node (ref "X1") (pin "4") (pinfunction "G1_4") (pintype "power_in"))
    )
    (net (code "55") (name "Net-(ANT1-PadFEED)") (class "Default")
      (node (ref "ANT1") (pin "FEED") (pinfunction "FEED_FEED") (pintype "passive"))
      (node (ref "C18") (pin "2") (pinfunction "2_2") (pintype "passive"))
      (node (ref "L1") (pin "1") (pinfunction "1_1") (pintype "passive"))
      (node (ref "L4") (pin "2") (pinfunction "2_2") (pintype "passive"))
    )
    (net (code "56") (name "Net-(C4-Pad2)") (class "Default")
      (node (ref "C4") (pin "2") (pinfunction "2_2") (pintype "passive"))
      (node (ref "L2") (pin "2") (pinfunction "2_2") (pintype "passive"))
      (node (ref "U3") (pin "2") (pinfunction "VDD3P3_2") (pintype "bidirectional"))
      (node (ref "U3") (pin "3") (pinfunction "VDD3P3_3") (pintype "bidirectional"))
    )
    (net (code "57") (name "Net-(C8-Pad2)") (class "Default")
      (node (ref "C8") (pin "2") (pinfunction "2_2") (pintype "passive"))
      (node (ref "L4") (pin "1") (pinfunction "1_1") (pintype "passive"))
    )
    (net (code "58") (name "Net-(PWR-Pad-)") (class "Default")
      (node (ref "PWR") (pin "-") (pinfunction "-_-") (pintype "passive"))
      (node (ref "R1") (pin "2") (pinfunction "2_2") (pintype "passive"))
    )
    (net (code "59") (name "Net-(Q2-B)") (class "Default")
      (node (ref "Q2") (pin "1") (pinfunction "B_1") (pintype "passive"))
      (node (ref "R17") (pin "1") (pinfunction "1_1") (pintype "passive"))
      (node (ref "R3") (pin "2") (pinfunction "2_2") (pintype "passive"))
    )
    (net (code "60") (name "Net-(R10-Pad1)") (class "Default")
      (node (ref "R10") (pin "1") (pinfunction "1_1") (pintype "passive"))
      (node (ref "R14") (pin "1") (pinfunction "1_1") (pintype "passive"))
      (node (ref "R17") (pin "2") (pinfunction "2_2") (pintype "passive"))
    )
    (net (code "61") (name "Net-(U3-LNA_IN)") (class "Default")
      (node (ref "C5") (pin "2") (pinfunction "2_2") (pintype "passive"))
      (node (ref "L1") (pin "2") (pinfunction "2_2") (pintype "passive"))
      (node (ref "U3") (pin "1") (pinfunction "LNA_IN_1") (pintype "bidirectional"))
    )
    (net (code "62") (name "Net-(U3-SPICLK)") (class "Default")
      (node (ref "R18") (pin "2") (pinfunction "2_2") (pintype "passive"))
      (node (ref "U3") (pin "33") (pinfunction "SPICLK_33") (pintype "bidirectional"))
    )
    (net (code "63") (name "Net-(U3-SPID)") (class "Default")
      (node (ref "R28") (pin "2") (pinfunction "2_2") (pintype "passive"))
      (node (ref "U3") (pin "35") (pinfunction "SPID_35") (pintype "bidirectional"))
    )
    (net (code "64") (name "Net-(U3-SPIHD)") (class "Default")
      (node (ref "R25") (pin "2") (pinfunction "2_2") (pintype "passive"))
      (node (ref "U3") (pin "30") (pinfunction "SPIHD_30") (pintype "bidirectional"))
    )
    (net (code "65") (name "Net-(U3-SPIQ)") (class "Default")
      (node (ref "R16") (pin "2") (pinfunction "2_2") (pintype "passive"))
      (node (ref "U3") (pin "34") (pinfunction "SPIQ_34") (pintype "bidirectional"))
    )
    (net (code "66") (name "Net-(U3-SPIWP)") (class "Default")
      (node (ref "R23") (pin "2") (pinfunction "2_2") (pintype "passive"))
      (node (ref "U3") (pin "31") (pinfunction "SPIWP_31") (pintype "bidirectional"))
    )
    (net (code "67") (name "Net-(U3-U0TXD)") (class "Default")
      (node (ref "R12") (pin "2") (pinfunction "2_2") (pintype "passive"))
      (node (ref "U3") (pin "49") (pinfunction "U0TXD_49") (pintype "bidirectional"))
    )
    (net (code "68") (name "Net-(U3-XTAL_N)") (class "Default")
      (node (ref "C13") (pin "2") (pinfunction "2_2") (pintype "passive"))
      (node (ref "U3") (pin "53") (pinfunction "XTAL_N_53") (pintype "bidirectional"))
      (node (ref "X1") (pin "3") (pinfunction "X2_3") (pintype "bidirectional"))
    )
    (net (code "69") (name "Net-(U3-XTAL_P)") (class "Default")
      (node (ref "R34") (pin "2") (pinfunction "2_2") (pintype "passive"))
      (node (ref "U3") (pin "54") (pinfunction "XTAL_P_54") (pintype "bidirectional"))
    )
    (net (code "70") (name "Net-(U5-BYP)") (class "Default")
      (node (ref "C7") (pin "2") (pinfunction "2_2") (pintype "passive"))
      (node (ref "U5") (pin "4") (pinfunction "BYP_4") (pintype "bidirectional"))
    )
    (net (code "71") (name "Net-(USB2-CC1)") (class "Default")
      (node (ref "R30") (pin "1") (pinfunction "1_1") (pintype "passive"))
      (node (ref "USB2") (pin "A5") (pinfunction "CC1_A5") (pintype "bidirectional"))
    )
    (net (code "72") (name "Net-(USB2-CC2)") (class "Default")
      (node (ref "R29") (pin "1") (pinfunction "1_1") (pintype "passive"))
      (node (ref "USB2") (pin "B5") (pinfunction "CC2_B5") (pintype "bidirectional"))
    )
    (net (code "73") (name "Net-(X1-X1)") (class "Default")
      (node (ref "C19") (pin "1") (pinfunction "1_1") (pintype "passive"))
      (node (ref "R34") (pin "1") (pinfunction "1_1") (pintype "passive"))
      (node (ref "X1") (pin "1") (pinfunction "X1_1") (pintype "bidirectional"))
    )
    (net (code "75") (name "unconnected-(CN1-Pad4)") (class "Default")
      (node (ref "CN1") (pin "4") (pinfunction "4_4") (pintype "bidirectional"))
    )
    (net (code "76") (name "unconnected-(P2-Pad11)") (class "Default")
      (node (ref "P2") (pin "11") (pinfunction "11_11") (pintype "bidirectional"))
    )
    (net (code "77") (name "unconnected-(P2-Pad23)") (class "Default")
      (node (ref "P2") (pin "23") (pinfunction "23_23") (pintype "bidirectional"))
    )
    (net (code "78") (name "unconnected-(U3-GPIO33-Pad38)") (class "Default")
      (node (ref "U3") (pin "38") (pinfunction "GPIO33_38") (pintype "bidirectional"))
    )
    (net (code "79") (name "unconnected-(U3-GPIO34-Pad39)") (class "Default")
      (node (ref "U3") (pin "39") (pinfunction "GPIO34_39") (pintype "bidirectional"))
    )
    (net (code "80") (name "unconnected-(U3-GPIO35-Pad40)") (class "Default")
      (node (ref "U3") (pin "40") (pinfunction "GPIO35_40") (pintype "bidirectional"))
    )
    (net (code "81") (name "unconnected-(U3-GPIO36-Pad41)") (class "Default")
      (node (ref "U3") (pin "41") (pinfunction "GPIO36_41") (pintype "bidirectional"))
    )
    (net (code "82") (name "unconnected-(U3-GPIO37-Pad42)") (class "Default")
      (node (ref "U3") (pin "42") (pinfunction "GPIO37_42") (pintype "bidirectional"))
    )
    (net (code "83") (name "unconnected-(USB2-SBU1-PadA8)") (class "Default")
      (node (ref "USB2") (pin "A8") (pinfunction "SBU1_A8") (pintype "bidirectional"))
    )
    (net (code "84") (name "unconnected-(USB2-SBU2-PadB8)") (class "Default")
      (node (ref "USB2") (pin "B8") (pinfunction "SBU2_B8") (pintype "bidirectional"))
    )
  )
)
